# MRCS-555-Tone-Generator.net
KiCad netlist of a schematic drawn in EAGLE
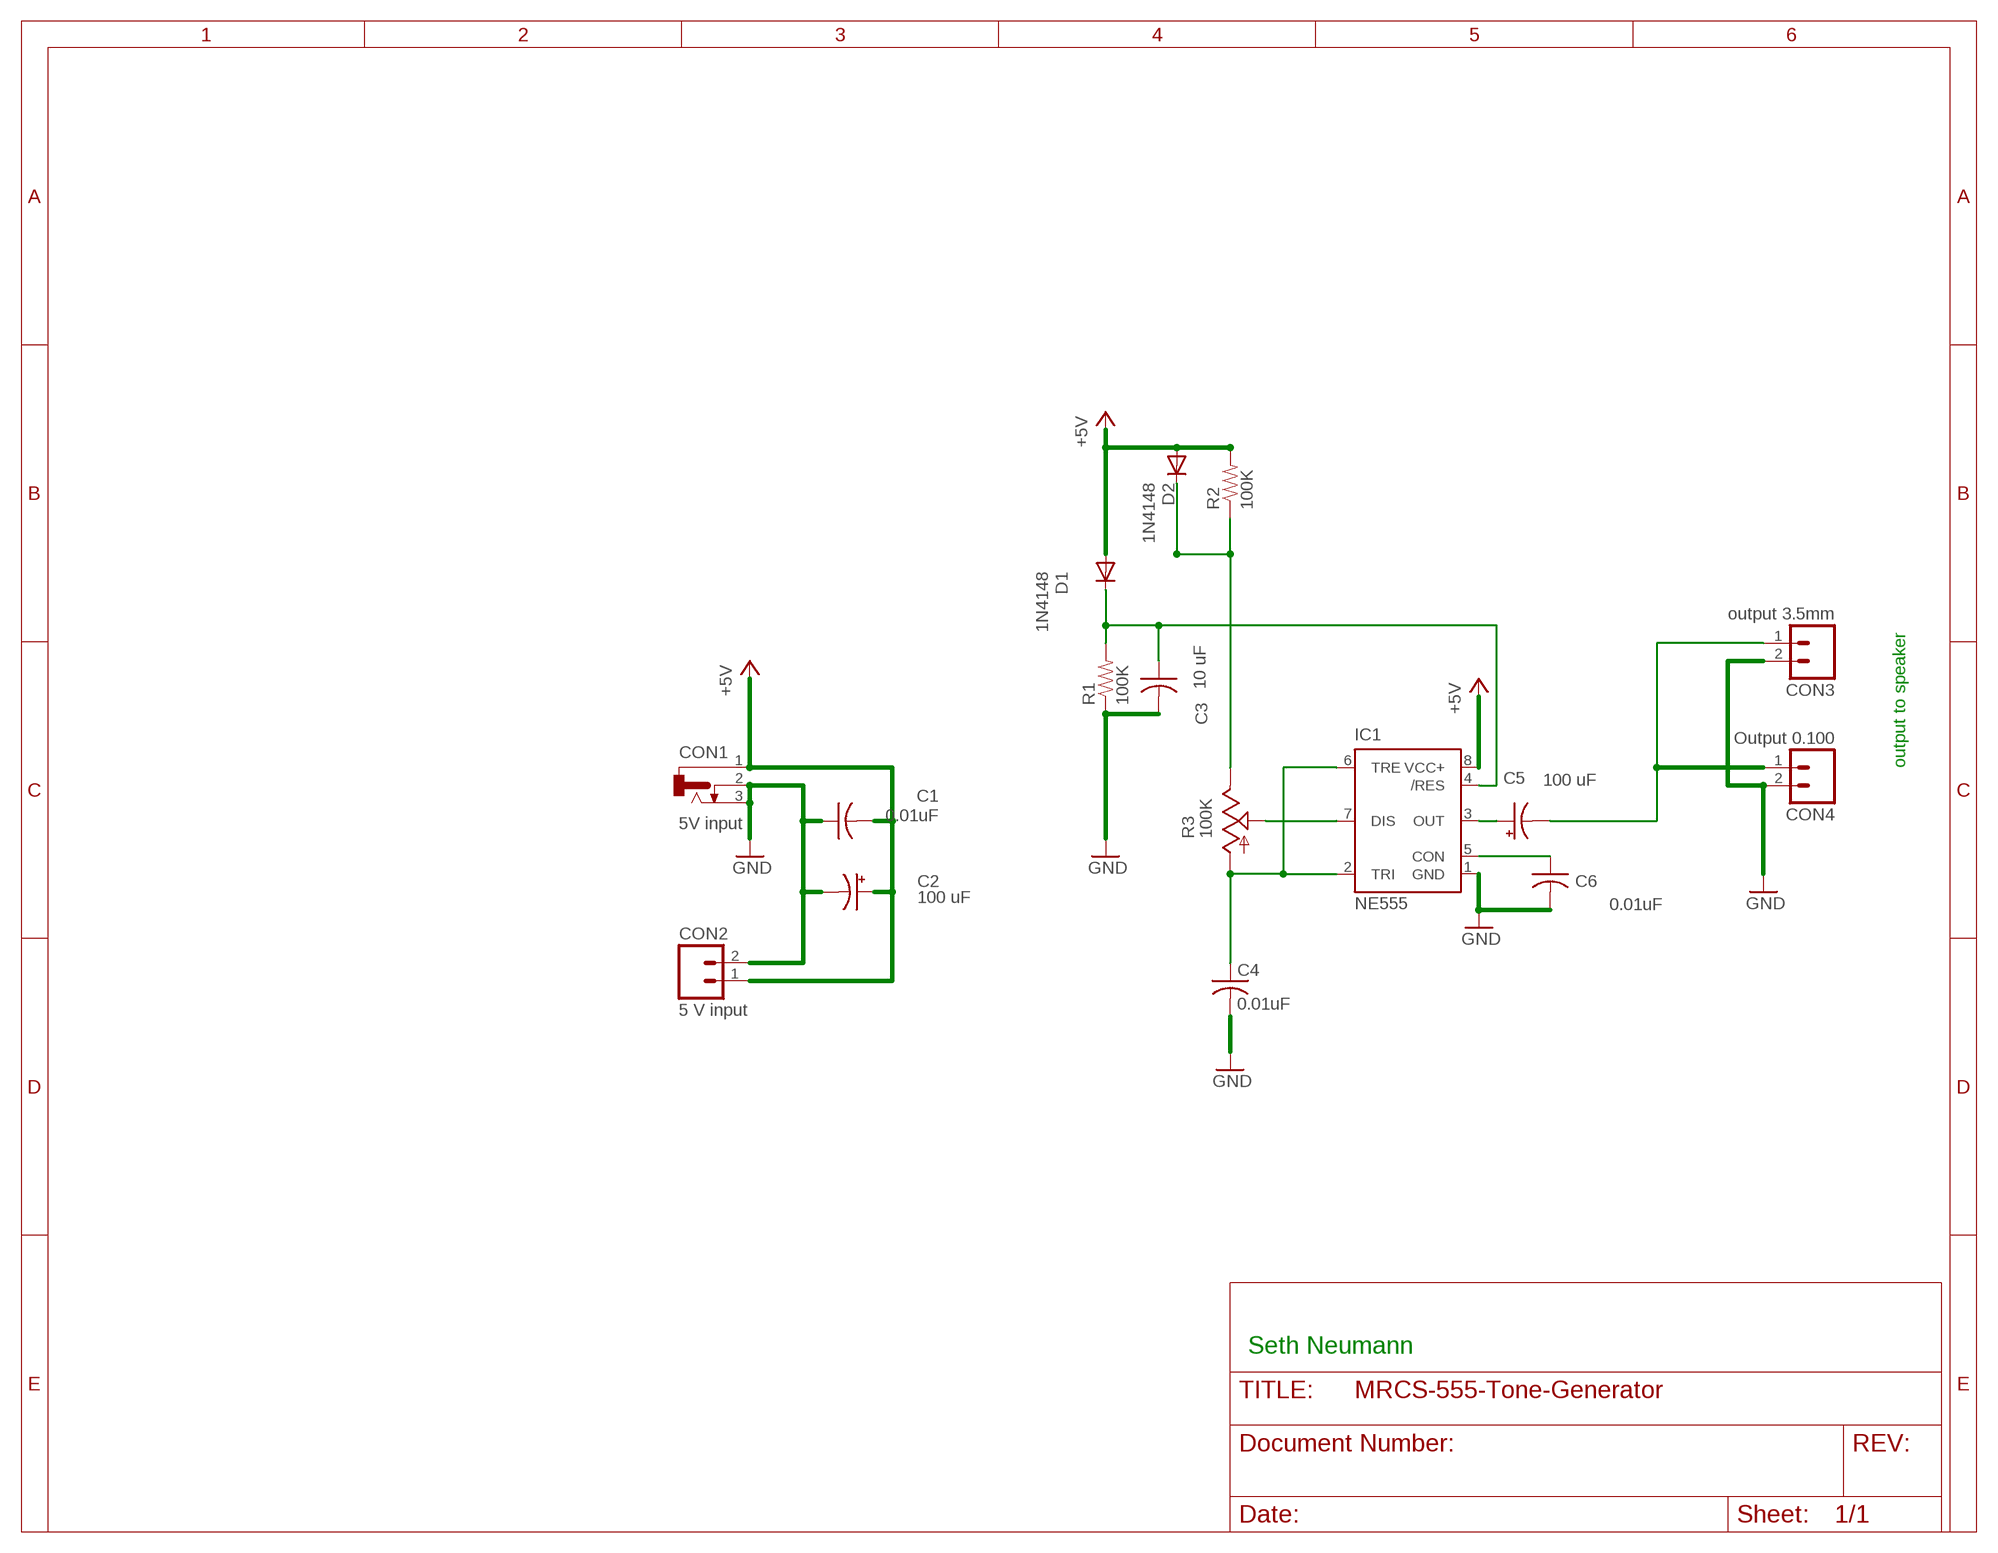
[diagram p0: schematic, sheet 1]

(export (version "E")
  (design (tool "Eeschema 10.0.6"))
  (components
    (comp (ref "C1")
      (value "0.01uF")
      (footprint "eagle-import:C-PTH-0.100")
      (libsource (lib "eagle-import") (part "CAPPTH2"))
    )
    (comp (ref "C2")
      (value "100 uF")
      (footprint "eagle-import:E3.5-10")
      (libsource (lib "eagle-import") (part "CAP-POLPTH-3.5MM"))
    )
    (comp (ref "C3")
      (value "10 uF")
      (footprint "eagle-import:C-PTH-0.100")
      (libsource (lib "eagle-import") (part "CAPPTH2"))
    )
    (comp (ref "C4")
      (value "0.01uF")
      (footprint "eagle-import:C-PTH-0.100")
      (libsource (lib "eagle-import") (part "CAPPTH2"))
    )
    (comp (ref "C5")
      (value "100 uF")
      (footprint "eagle-import:E3.5-10")
      (libsource (lib "eagle-import") (part "CAP-POLPTH-3.5MM"))
    )
    (comp (ref "C6")
      (value "0.01uF")
      (footprint "eagle-import:C-PTH-0.100")
      (libsource (lib "eagle-import") (part "CAPPTH2"))
    )
    (comp (ref "CON1")
      (value "5V input")
      (footprint "eagle-import:DCJ0202")
      (libsource (lib "eagle-import") (part "CONNECTOR-DC-POWER-RA"))
    )
    (comp (ref "CON2")
      (value "5 V input")
      (footprint "eagle-import:1X02_LOCK")
      (libsource (lib "eagle-import") (part "CONNECTOR-M021X02-LOCK"))
    )
    (comp (ref "CON3")
      (value "output 3.5mm")
      (footprint "eagle-import:SCREWTERMINAL-3.5MM-2_LOCK")
      (libsource (lib "eagle-import") (part "CONNECTOR-M023.5MM-LOCK"))
    )
    (comp (ref "CON4")
      (value "Output 0.100")
      (footprint "eagle-import:1X02_LOCK")
      (libsource (lib "eagle-import") (part "CONNECTOR-M021X02-LOCK"))
    )
    (comp (ref "D1")
      (value "1N4148")
      (footprint "eagle-import:DIODE-1N4148")
      (libsource (lib "eagle-import") (part "DIODE1N4148"))
    )
    (comp (ref "D2")
      (value "1N4148")
      (footprint "eagle-import:DIODE-1N4148")
      (libsource (lib "eagle-import") (part "DIODE1N4148"))
    )
    (comp (ref "IC1")
      (value "NE555")
      (footprint "eagle-import:DIL-08")
      (fields (field (name "MF") "Arrow Electronics") (field (name "MPN") "NE555N"))
      (libsource (lib "eagle-import") (part "NE555P"))
    )
    (comp (ref "R1")
      (value "100K")
      (footprint "eagle-import:AXIAL-0.4-RES")
      (libsource (lib "eagle-import") (part "RPTH04"))
    )
    (comp (ref "R2")
      (value "100K")
      (footprint "eagle-import:AXIAL-0.4-RES")
      (libsource (lib "eagle-import") (part "RPTH04"))
    )
    (comp (ref "R3")
      (value "100K")
      (footprint "eagle-import:RS3")
      (libsource (lib "eagle-import") (part "TRIM_US-RS3"))
    )
  )
  (nets
    (net (code "1") (name "+5V") (class "Default")
      (node (ref "C1") (pin "2") (pinfunction "2_2") (pintype "passive"))
      (node (ref "C2") (pin "+") (pinfunction "+_+") (pintype "passive"))
      (node (ref "CON1") (pin "1") (pinfunction "1_1") (pintype "passive"))
      (node (ref "CON2") (pin "1") (pinfunction "A_1") (pintype "passive"))
      (node (ref "D1") (pin "A") (pinfunction "A_A") (pintype "passive"))
      (node (ref "D2") (pin "A") (pinfunction "A_A") (pintype "passive"))
      (node (ref "IC1") (pin "8") (pinfunction "VCC+_8") (pintype "power_in"))
      (node (ref "R2") (pin "P$2") (pinfunction "2_P$2") (pintype "passive"))
    )
    (net (code "2") (name "GND") (class "Default")
      (node (ref "C1") (pin "1") (pinfunction "1_1") (pintype "passive"))
      (node (ref "C2") (pin "-") (pinfunction "-_-") (pintype "passive"))
      (node (ref "C3") (pin "2") (pinfunction "2_2") (pintype "passive"))
      (node (ref "C4") (pin "2") (pinfunction "2_2") (pintype "passive"))
      (node (ref "C6") (pin "2") (pinfunction "2_2") (pintype "passive"))
      (node (ref "CON1") (pin "2") (pinfunction "2_2") (pintype "passive"))
      (node (ref "CON1") (pin "3") (pinfunction "3_3") (pintype "passive"))
      (node (ref "CON2") (pin "2") (pinfunction "B_2") (pintype "passive"))
      (node (ref "CON3") (pin "2") (pinfunction "B_2") (pintype "passive"))
      (node (ref "CON4") (pin "2") (pinfunction "B_2") (pintype "passive"))
      (node (ref "IC1") (pin "1") (pinfunction "GND_1") (pintype "power_in"))
      (node (ref "R1") (pin "P$1") (pinfunction "1_P$1") (pintype "passive"))
    )
    (net (code "3") (name "Net-(CON3-A)") (class "Default")
      (node (ref "C5") (pin "-") (pinfunction "-_-") (pintype "passive"))
      (node (ref "CON3") (pin "1") (pinfunction "A_1") (pintype "passive"))
      (node (ref "CON4") (pin "1") (pinfunction "A_1") (pintype "passive"))
    )
    (net (code "4") (name "Net-(IC1-CON)") (class "Default")
      (node (ref "C6") (pin "1") (pinfunction "1_1") (pintype "passive"))
      (node (ref "IC1") (pin "5") (pinfunction "CON_5") (pintype "input"))
    )
    (net (code "5") (name "Net-(IC1-DIS)") (class "Default")
      (node (ref "IC1") (pin "7") (pinfunction "DIS_7") (pintype "input"))
      (node (ref "R3") (pin "S") (pinfunction "S_S") (pintype "passive"))
    )
    (net (code "6") (name "Net-(IC1-OUT)") (class "Default")
      (node (ref "C5") (pin "+") (pinfunction "+_+") (pintype "passive"))
      (node (ref "IC1") (pin "3") (pinfunction "OUT_3") (pintype "output"))
    )
    (net (code "7") (name "Net-(IC1-TRE)") (class "Default")
      (node (ref "C4") (pin "1") (pinfunction "1_1") (pintype "passive"))
      (node (ref "IC1") (pin "2") (pinfunction "TRI_2") (pintype "input"))
      (node (ref "IC1") (pin "6") (pinfunction "TRE_6") (pintype "input"))
      (node (ref "R3") (pin "A") (pinfunction "A_A") (pintype "passive"))
    )
    (net (code "8") (name "Net-(IC1-{slash}RES)") (class "Default")
      (node (ref "C3") (pin "1") (pinfunction "1_1") (pintype "passive"))
      (node (ref "D1") (pin "C") (pinfunction "C_C") (pintype "passive"))
      (node (ref "IC1") (pin "4") (pinfunction "/RES_4") (pintype "input"))
      (node (ref "R1") (pin "P$2") (pinfunction "2_P$2") (pintype "passive"))
    )
    (net (code "9") (name "Net-(R2-1)") (class "Default")
      (node (ref "D2") (pin "C") (pinfunction "C_C") (pintype "passive"))
      (node (ref "R2") (pin "P$1") (pinfunction "1_P$1") (pintype "passive"))
      (node (ref "R3") (pin "E") (pinfunction "E_E") (pintype "passive"))
    )
  )
)
